# PowerLevel.net
KiCad netlist of a schematic drawn in EAGLE
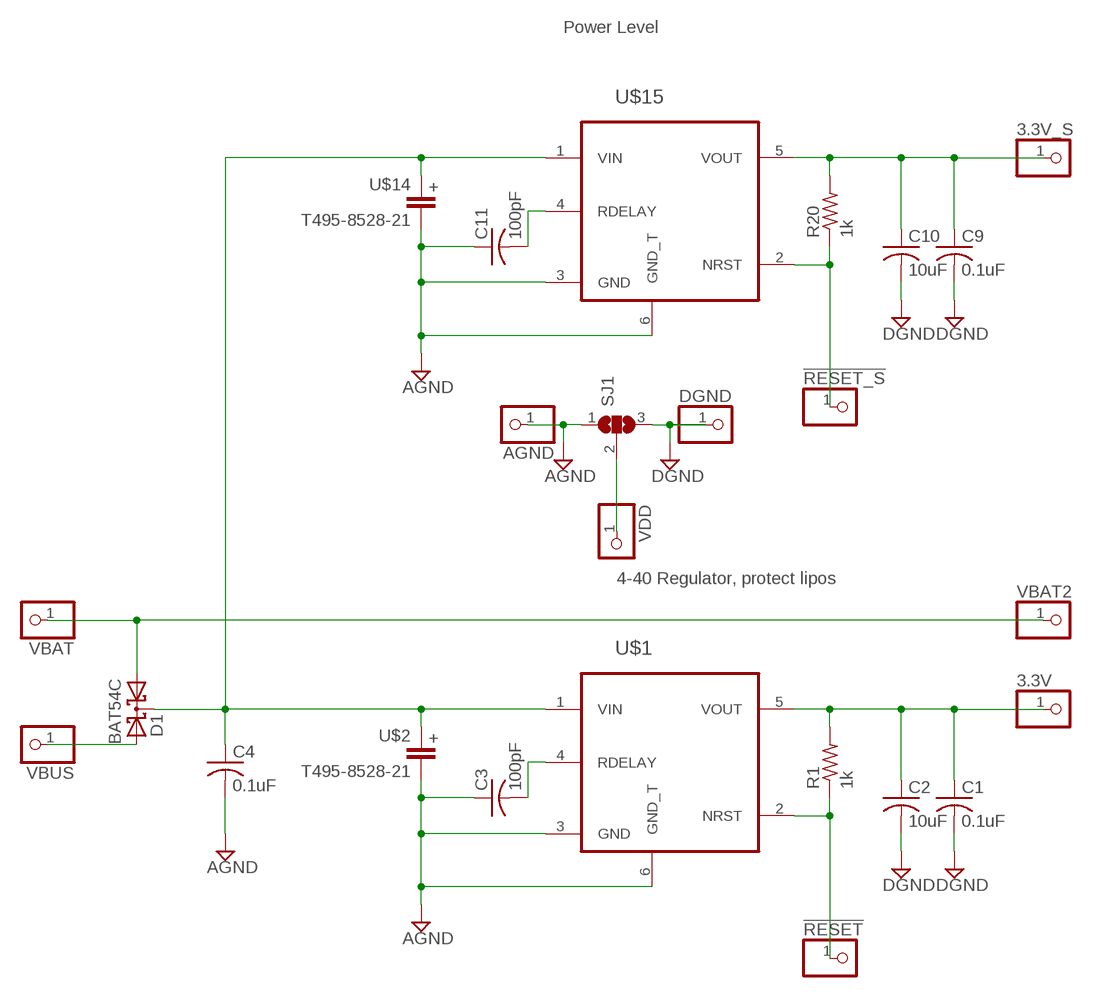
[diagram p0: schematic, sheet 1]

(export (version "E")
  (design (tool "Eeschema 10.0.6"))
  (components
    (comp (ref "!RESET")
      (value "PINHD-1X1")
      (footprint "eagle-import:1X01")
      (libsource (lib "eagle-import") (part "PINHD-1X1"))
    )
    (comp (ref "!RESET_S")
      (value "PINHD-1X1")
      (footprint "eagle-import:1X01")
      (libsource (lib "eagle-import") (part "PINHD-1X1"))
    )
    (comp (ref "3.3V")
      (value "PINHD-1X1")
      (footprint "eagle-import:1X01")
      (libsource (lib "eagle-import") (part "PINHD-1X1"))
    )
    (comp (ref "3.3V_S")
      (value "PINHD-1X1")
      (footprint "eagle-import:1X01")
      (libsource (lib "eagle-import") (part "PINHD-1X1"))
    )
    (comp (ref "AGND")
      (value "PINHD-1X1")
      (footprint "eagle-import:1X01")
      (libsource (lib "eagle-import") (part "PINHD-1X1"))
    )
    (comp (ref "C1")
      (value "0.1uF")
      (footprint "eagle-import:C0402")
      (libsource (lib "eagle-import") (part "C-USC0402"))
    )
    (comp (ref "C2")
      (value "10uF")
      (footprint "eagle-import:C0402")
      (libsource (lib "eagle-import") (part "C-USC0402"))
    )
    (comp (ref "C3")
      (value "100pF")
      (footprint "eagle-import:C0402K")
      (libsource (lib "eagle-import") (part "C-USC0402K"))
    )
    (comp (ref "C4")
      (value "0.1uF")
      (footprint "eagle-import:C0402K")
      (libsource (lib "eagle-import") (part "C-USC0402K"))
    )
    (comp (ref "C9")
      (value "0.1uF")
      (footprint "eagle-import:C0402")
      (libsource (lib "eagle-import") (part "C-USC0402"))
    )
    (comp (ref "C10")
      (value "10uF")
      (footprint "eagle-import:C0402")
      (libsource (lib "eagle-import") (part "C-USC0402"))
    )
    (comp (ref "C11")
      (value "100pF")
      (footprint "eagle-import:C0402K")
      (libsource (lib "eagle-import") (part "C-USC0402K"))
    )
    (comp (ref "D1")
      (value "BAT54C")
      (footprint "eagle-import:SOT23")
      (libsource (lib "eagle-import") (part "BAT54C"))
    )
    (comp (ref "DGND")
      (value "PINHD-1X1")
      (footprint "eagle-import:1X01")
      (libsource (lib "eagle-import") (part "PINHD-1X1"))
    )
    (comp (ref "R1")
      (value "1k")
      (footprint "eagle-import:R0402")
      (libsource (lib "eagle-import") (part "R-US_R0402"))
    )
    (comp (ref "R20")
      (value "1k")
      (footprint "eagle-import:R0402")
      (libsource (lib "eagle-import") (part "R-US_R0402"))
    )
    (comp (ref "SJ1")
      (value "SJ2WW")
      (footprint "eagle-import:SJ_2W")
      (libsource (lib "eagle-import") (part "SJ2WW"))
    )
    (comp (ref "U$1")
      (value "TPS7A6033-Q1")
      (footprint "eagle-import:TO-263-5")
      (libsource (lib "eagle-import") (part "TPS7A6033-Q1"))
    )
    (comp (ref "U$2")
      (value "T495-8528-21")
      (footprint "eagle-import:8528-21")
      (libsource (lib "eagle-import") (part "T495-8528-21"))
    )
    (comp (ref "U$14")
      (value "T495-8528-21")
      (footprint "eagle-import:8528-21")
      (libsource (lib "eagle-import") (part "T495-8528-21"))
    )
    (comp (ref "U$15")
      (value "TPS7A6033-Q1")
      (footprint "eagle-import:TO-263-5")
      (libsource (lib "eagle-import") (part "TPS7A6033-Q1"))
    )
    (comp (ref "VBAT")
      (value "PINHD-1X1")
      (footprint "eagle-import:1X01")
      (libsource (lib "eagle-import") (part "PINHD-1X1"))
    )
    (comp (ref "VBAT2")
      (value "PINHD-1X1")
      (footprint "eagle-import:1X01")
      (libsource (lib "eagle-import") (part "PINHD-1X1"))
    )
    (comp (ref "VBUS")
      (value "PINHD-1X1")
      (footprint "eagle-import:1X01")
      (libsource (lib "eagle-import") (part "PINHD-1X1"))
    )
    (comp (ref "VDD")
      (value "PINHD-1X1")
      (footprint "eagle-import:1X01")
      (libsource (lib "eagle-import") (part "PINHD-1X1"))
    )
  )
  (nets
    (net (code "1") (name "AGND") (class "Default")
      (node (ref "AGND") (pin "1") (pinfunction "1_1") (pintype "passive"))
      (node (ref "C11") (pin "1") (pinfunction "1_1") (pintype "passive"))
      (node (ref "C3") (pin "1") (pinfunction "1_1") (pintype "passive"))
      (node (ref "C4") (pin "2") (pinfunction "2_2") (pintype "passive"))
      (node (ref "SJ1") (pin "1") (pinfunction "1_1") (pintype "passive"))
      (node (ref "U$1") (pin "3") (pinfunction "GND_3") (pintype "passive"))
      (node (ref "U$1") (pin "6") (pinfunction "GND_T_6") (pintype "passive"))
      (node (ref "U$14") (pin "NEG") (pinfunction "2_NEG") (pintype "passive"))
      (node (ref "U$15") (pin "3") (pinfunction "GND_3") (pintype "passive"))
      (node (ref "U$15") (pin "6") (pinfunction "GND_T_6") (pintype "passive"))
      (node (ref "U$2") (pin "NEG") (pinfunction "2_NEG") (pintype "passive"))
    )
    (net (code "2") (name "DGND") (class "Default")
      (node (ref "C1") (pin "2") (pinfunction "2_2") (pintype "passive"))
      (node (ref "C10") (pin "2") (pinfunction "2_2") (pintype "passive"))
      (node (ref "C2") (pin "2") (pinfunction "2_2") (pintype "passive"))
      (node (ref "C9") (pin "2") (pinfunction "2_2") (pintype "passive"))
      (node (ref "DGND") (pin "1") (pinfunction "1_1") (pintype "passive"))
      (node (ref "SJ1") (pin "3") (pinfunction "3_3") (pintype "passive"))
    )
    (net (code "3") (name "Net-(D1-A1)") (class "Default")
      (node (ref "D1") (pin "1") (pinfunction "A1_1") (pintype "passive"))
      (node (ref "VBAT") (pin "1") (pinfunction "1_1") (pintype "passive"))
      (node (ref "VBAT2") (pin "1") (pinfunction "1_1") (pintype "passive"))
    )
    (net (code "4") (name "Net-(D1-A2)") (class "Default")
      (node (ref "D1") (pin "2") (pinfunction "A2_2") (pintype "passive"))
      (node (ref "VBUS") (pin "1") (pinfunction "1_1") (pintype "passive"))
    )
    (net (code "5") (name "Net-(D1-CC)") (class "Default")
      (node (ref "C4") (pin "1") (pinfunction "1_1") (pintype "passive"))
      (node (ref "D1") (pin "3") (pinfunction "CC_3") (pintype "passive"))
      (node (ref "U$1") (pin "1") (pinfunction "VIN_1") (pintype "power_in"))
      (node (ref "U$14") (pin "POS") (pinfunction "1_POS") (pintype "passive"))
      (node (ref "U$15") (pin "1") (pinfunction "VIN_1") (pintype "power_in"))
      (node (ref "U$2") (pin "POS") (pinfunction "1_POS") (pintype "passive"))
    )
    (net (code "6") (name "Net-(SJ1-Pad2)") (class "Default")
      (node (ref "SJ1") (pin "2") (pinfunction "2_2") (pintype "passive"))
      (node (ref "VDD") (pin "1") (pinfunction "1_1") (pintype "passive"))
    )
    (net (code "7") (name "Net-(U$1-NRST)") (class "Default")
      (node (ref "!RESET") (pin "1") (pinfunction "1_1") (pintype "passive"))
      (node (ref "R1") (pin "1") (pinfunction "1_1") (pintype "passive"))
      (node (ref "U$1") (pin "2") (pinfunction "NRST_2") (pintype "output"))
    )
    (net (code "8") (name "Net-(U$1-RDELAY)") (class "Default")
      (node (ref "C3") (pin "2") (pinfunction "2_2") (pintype "passive"))
      (node (ref "U$1") (pin "4") (pinfunction "RDELAY_4") (pintype "output"))
    )
    (net (code "9") (name "Net-(U$1-VOUT)") (class "Default")
      (node (ref "3.3V") (pin "1") (pinfunction "1_1") (pintype "passive"))
      (node (ref "C1") (pin "1") (pinfunction "1_1") (pintype "passive"))
      (node (ref "C2") (pin "1") (pinfunction "1_1") (pintype "passive"))
      (node (ref "R1") (pin "2") (pinfunction "2_2") (pintype "passive"))
      (node (ref "U$1") (pin "5") (pinfunction "VOUT_5") (pintype "output"))
    )
    (net (code "10") (name "Net-(U$15-NRST)") (class "Default")
      (node (ref "!RESET_S") (pin "1") (pinfunction "1_1") (pintype "passive"))
      (node (ref "R20") (pin "1") (pinfunction "1_1") (pintype "passive"))
      (node (ref "U$15") (pin "2") (pinfunction "NRST_2") (pintype "output"))
    )
    (net (code "11") (name "Net-(U$15-RDELAY)") (class "Default")
      (node (ref "C11") (pin "2") (pinfunction "2_2") (pintype "passive"))
      (node (ref "U$15") (pin "4") (pinfunction "RDELAY_4") (pintype "output"))
    )
    (net (code "12") (name "Net-(U$15-VOUT)") (class "Default")
      (node (ref "3.3V_S") (pin "1") (pinfunction "1_1") (pintype "passive"))
      (node (ref "C10") (pin "1") (pinfunction "1_1") (pintype "passive"))
      (node (ref "C9") (pin "1") (pinfunction "1_1") (pintype "passive"))
      (node (ref "R20") (pin "2") (pinfunction "2_2") (pintype "passive"))
      (node (ref "U$15") (pin "5") (pinfunction "VOUT_5") (pintype "output"))
    )
  )
)
